# 04_excitation.net
KiCad netlist of a schematic drawn in Altium Designer
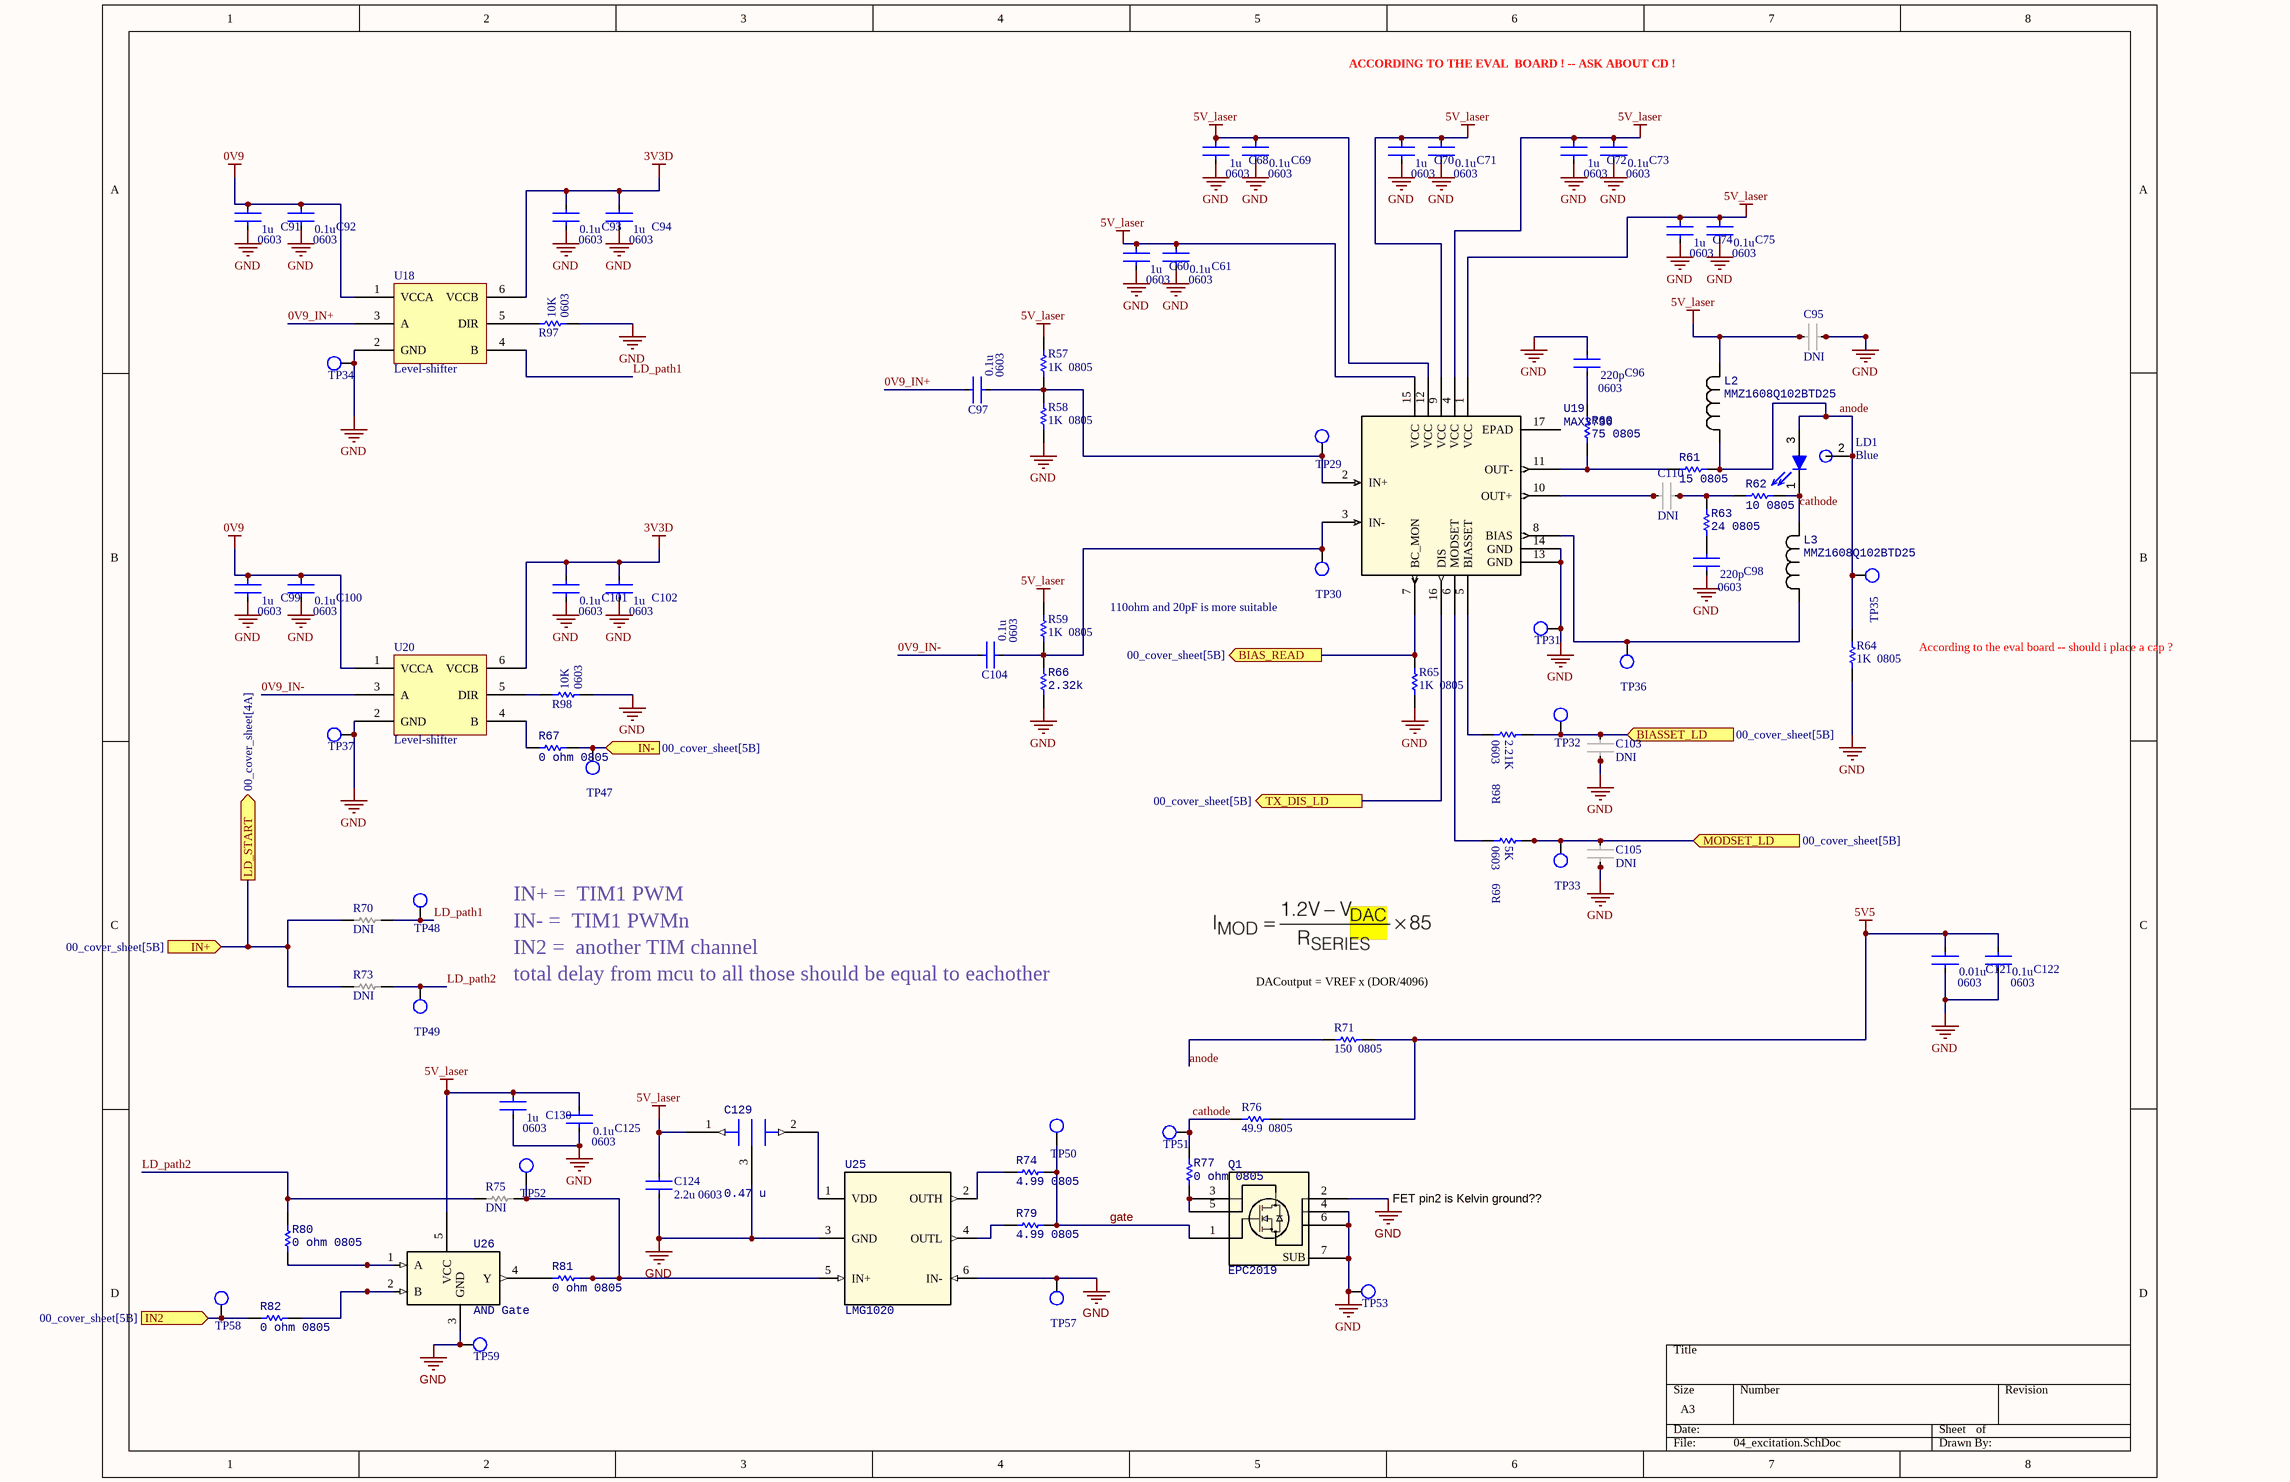
[diagram p0: 04_excitation.SchDoc]

(export (version "E")
  (design (tool "Eeschema 10.0.6"))
  (components
    (comp (ref "C60")
      (value "C1608X5R1E105K080AC")
      (footprint "CAPTDK0603")
      (description "CAP CER 1UF 25V X5R 0603")
      (libsource (lib "tcspc00") (part "C1608X5R1E105K080AC"))
    )
    (comp (ref "C61")
      (value "CGA3E2X7R1H104K080AA")
      (footprint "CAPTDK0603")
      (description "CAP CER 0.1UF 50V X7R 0603")
      (libsource (lib "tcspc00") (part "CGA3E2X7R1H104K080AA"))
    )
    (comp (ref "C68")
      (value "C1608X5R1E105K080AC")
      (footprint "CAPTDK0603")
      (description "CAP CER 1UF 25V X5R 0603")
      (libsource (lib "tcspc00") (part "C1608X5R1E105K080AC"))
    )
    (comp (ref "C69")
      (value "CGA3E2X7R1H104K080AA")
      (footprint "CAPTDK0603")
      (description "CAP CER 0.1UF 50V X7R 0603")
      (libsource (lib "tcspc00") (part "CGA3E2X7R1H104K080AA"))
    )
    (comp (ref "C70")
      (value "C1608X5R1E105K080AC")
      (footprint "CAPTDK0603")
      (description "CAP CER 1UF 25V X5R 0603")
      (libsource (lib "tcspc00") (part "C1608X5R1E105K080AC"))
    )
    (comp (ref "C71")
      (value "CGA3E2X7R1H104K080AA")
      (footprint "CAPTDK0603")
      (description "CAP CER 0.1UF 50V X7R 0603")
      (libsource (lib "tcspc00") (part "CGA3E2X7R1H104K080AA"))
    )
    (comp (ref "C72")
      (value "C1608X5R1E105K080AC")
      (footprint "CAPTDK0603")
      (description "CAP CER 1UF 25V X5R 0603")
      (libsource (lib "tcspc00") (part "C1608X5R1E105K080AC"))
    )
    (comp (ref "C73")
      (value "CGA3E2X7R1H104K080AA")
      (footprint "CAPTDK0603")
      (description "CAP CER 0.1UF 50V X7R 0603")
      (libsource (lib "tcspc00") (part "CGA3E2X7R1H104K080AA"))
    )
    (comp (ref "C74")
      (value "C1608X5R1E105K080AC")
      (footprint "CAPTDK0603")
      (description "CAP CER 1UF 25V X5R 0603")
      (libsource (lib "tcspc00") (part "C1608X5R1E105K080AC"))
    )
    (comp (ref "C75")
      (value "CGA3E2X7R1H104K080AA")
      (footprint "CAPTDK0603")
      (description "CAP CER 0.1UF 50V X7R 0603")
      (libsource (lib "tcspc00") (part "CGA3E2X7R1H104K080AA"))
    )
    (comp (ref "C91")
      (value "C1608X5R1E105K080AC")
      (footprint "CAPTDK0603")
      (description "CAP CER 1UF 25V X5R 0603")
      (libsource (lib "tcspc00") (part "C1608X5R1E105K080AC"))
    )
    (comp (ref "C92")
      (value "CGA3E2X7R1H104K080AA")
      (footprint "CAPTDK0603")
      (description "CAP CER 0.1UF 50V X7R 0603")
      (libsource (lib "tcspc00") (part "CGA3E2X7R1H104K080AA"))
    )
    (comp (ref "C93")
      (value "CGA3E2X7R1H104K080AA")
      (footprint "CAPTDK0603")
      (description "CAP CER 0.1UF 50V X7R 0603")
      (libsource (lib "tcspc00") (part "CGA3E2X7R1H104K080AA"))
    )
    (comp (ref "C94")
      (value "C1608X5R1E105K080AC")
      (footprint "CAPTDK0603")
      (description "CAP CER 1UF 25V X5R 0603")
      (libsource (lib "tcspc00") (part "C1608X5R1E105K080AC"))
    )
    (comp (ref "C95")
      (value "DNI")
      (footprint "CAPTDK0603")
      (description "CAP PROVISION 0603")
      (libsource (lib "tcspc00") (part "C0402_PROVISION"))
    )
    (comp (ref "C96")
      (value "C0603C221K5RAC7867")
      (footprint "CAPTDK0603")
      (description "CAP CER 220PF 50V X7R 0603")
      (libsource (lib "tcspc00") (part "C0603C221K5RAC7867"))
    )
    (comp (ref "C97")
      (value "CGA3E2X7R1H104K080AA")
      (footprint "CAPTDK0603")
      (description "CAP CER 0.1UF 50V X7R 0603")
      (libsource (lib "tcspc00") (part "CGA3E2X7R1H104K080AA"))
    )
    (comp (ref "C98")
      (value "C0603C221K5RAC7867")
      (footprint "CAPTDK0603")
      (description "CAP CER 220PF 50V X7R 0603")
      (libsource (lib "tcspc00") (part "C0603C221K5RAC7867"))
    )
    (comp (ref "C99")
      (value "C1608X5R1E105K080AC")
      (footprint "CAPTDK0603")
      (description "CAP CER 1UF 25V X5R 0603")
      (libsource (lib "tcspc00") (part "C1608X5R1E105K080AC"))
    )
    (comp (ref "C100")
      (value "CGA3E2X7R1H104K080AA")
      (footprint "CAPTDK0603")
      (description "CAP CER 0.1UF 50V X7R 0603")
      (libsource (lib "tcspc00") (part "CGA3E2X7R1H104K080AA"))
    )
    (comp (ref "C101")
      (value "CGA3E2X7R1H104K080AA")
      (footprint "CAPTDK0603")
      (description "CAP CER 0.1UF 50V X7R 0603")
      (libsource (lib "tcspc00") (part "CGA3E2X7R1H104K080AA"))
    )
    (comp (ref "C102")
      (value "C1608X5R1E105K080AC")
      (footprint "CAPTDK0603")
      (description "CAP CER 1UF 25V X5R 0603")
      (libsource (lib "tcspc00") (part "C1608X5R1E105K080AC"))
    )
    (comp (ref "C103")
      (value "DNI")
      (footprint "CAPTDK0603")
      (description "CAP PROVISION 0603")
      (libsource (lib "tcspc00") (part "C0402_PROVISION"))
    )
    (comp (ref "C104")
      (value "CGA3E2X7R1H104K080AA")
      (footprint "CAPTDK0603")
      (description "CAP CER 0.1UF 50V X7R 0603")
      (libsource (lib "tcspc00") (part "CGA3E2X7R1H104K080AA"))
    )
    (comp (ref "C105")
      (value "DNI")
      (footprint "CAPTDK0603")
      (description "CAP PROVISION 0603")
      (libsource (lib "tcspc00") (part "C0402_PROVISION"))
    )
    (comp (ref "C110")
      (value "DNI")
      (footprint "CAPTDK0603")
      (description "CAP PROVISION 0603")
      (libsource (lib "tcspc00") (part "C0402_PROVISION"))
    )
    (comp (ref "C121")
      (value "C0603C103J5RACTU")
      (footprint "CAPTDK0603")
      (description "CAP CER 10000PF 50V X7R 0603")
      (libsource (lib "tcspc00") (part "C0603C103J5RACTU"))
    )
    (comp (ref "C122")
      (value "CGA3E2X7R1H104K080AA")
      (footprint "CAPTDK0603")
      (description "CAP CER 0.1UF 50V X7R 0603")
      (libsource (lib "tcspc00") (part "CGA3E2X7R1H104K080AA"))
    )
    (comp (ref "C124")
      (value "2.2u 0603")
      (footprint "CAPTDK0603")
      (description "CAP CER 2.2UF 0603")
      (libsource (lib "tcspc00") (part "CAP2u2"))
    )
    (comp (ref "C125")
      (value "CGA3E2X7R1H104K080AA")
      (footprint "CAPTDK0603")
      (description "CAP CER 0.1UF 50V X7R 0603")
      (libsource (lib "tcspc00") (part "CGA3E2X7R1H104K080AA"))
    )
    (comp (ref "C129")
      (value "0.47 u")
      (footprint "YFF18PW")
      (description "YFF18PW0J474MT0H0N CAP FEEDTHRU 0.47UF 6.3V 0603")
      (libsource (lib "tcspc00") (part "YFF18PW0J474MT0H0N"))
    )
    (comp (ref "C130")
      (value "C1608X5R1E105K080AC")
      (footprint "CAPTDK0603")
      (description "CAP CER 1UF 25V X5R 0603")
      (libsource (lib "tcspc00") (part "C1608X5R1E105K080AC"))
    )
    (comp (ref "L2")
      (value "MMZ1608Q102BTD25")
      (footprint "IND_TDK_MMZ1608_TDK")
      (description "FERRITE BEAD 1K OHM 0603 1LN")
      (libsource (lib "tcspc00") (part "MMZ1608Q102BTD25"))
    )
    (comp (ref "L3")
      (value "MMZ1608Q102BTD25")
      (footprint "IND_TDK_MMZ1608_TDK")
      (description "FERRITE BEAD 1K OHM 0603 1LN")
      (libsource (lib "tcspc00") (part "MMZ1608Q102BTD25"))
    )
    (comp (ref "LD1") (value "Blue") (footprint "LS56HBSM1") (libsource (lib "tcspc00") (part "LA_LS56HB")))
    (comp (ref "Q1")
      (value "EPC2019")
      (footprint "EPC2019_ECC")
      (description "GANFET N-CH 200V 8.5A DIE N-Channel 200 V 8.5A (Ta) Surface Mount Die")
      (libsource (lib "tcspc00") (part "EPC2019"))
    )
    (comp (ref "R57")
      (value "1K  0805")
      (footprint "RES-STACK-POLE-0805")
      (description "RES 1K OHM 1% 1/4W 0805")
      (libsource (lib "tcspc00") (part "RK73H2ATTD1001F"))
    )
    (comp (ref "R58")
      (value "1K  0805")
      (footprint "RES-STACK-POLE-0805")
      (description "RES 1K OHM 1% 1/4W 0805")
      (libsource (lib "tcspc00") (part "RK73H2ATTD1001F"))
    )
    (comp (ref "R59")
      (value "1K  0805")
      (footprint "RES-STACK-POLE-0805")
      (description "RES 1K OHM 1% 1/4W 0805")
      (libsource (lib "tcspc00") (part "RK73H2ATTD1001F"))
    )
    (comp (ref "R60")
      (value "75 0805")
      (footprint "RES-STACK-POLE-0805")
      (description "RES 75 OHM 1% 1/4W 0805")
      (libsource (lib "tcspc00") (part "RK73H2ATTD75R0F"))
    )
    (comp (ref "R61")
      (value "15 0805")
      (footprint "RES-STACK-POLE-0805")
      (description "RES 15 OHM 1% 1/4W 0805")
      (libsource (lib "tcspc00") (part "RK73H2ATTD15R0F"))
    )
    (comp (ref "R62")
      (value "10 0805")
      (footprint "RES-STACK-POLE-0805")
      (description "RES 10 OHM 1% 1/4W 0805")
      (libsource (lib "tcspc00") (part "RK73H2ATTD10R0F"))
    )
    (comp (ref "R63")
      (value "24 0805")
      (footprint "RES-STACK-POLE-0805")
      (description "RES 24 OHM 1% 1/4W 0805")
      (libsource (lib "tcspc00") (part "RK73H2ATTD24R0F"))
    )
    (comp (ref "R64")
      (value "1K  0805")
      (footprint "RES-STACK-POLE-0805")
      (description "RES 1K OHM 1% 1/4W 0805")
      (libsource (lib "tcspc00") (part "RK73H2ATTD1001F"))
    )
    (comp (ref "R65")
      (value "1K  0805")
      (footprint "RES-STACK-POLE-0805")
      (description "RK73H2ATK001KIT %1 tolerance resistors 0805")
      (libsource (lib "tcspc00") (part "RK73H2AT1001F"))
    )
    (comp (ref "R66")
      (value "2.32k")
      (footprint "RES-STACK-POLE-0805")
      (description "RES 2.32K OHM 1% 1/4W 0805")
      (libsource (lib "tcspc00") (part "RK73H2ATTD2321F"))
    )
    (comp (ref "R67")
      (value "0 ohm 0805")
      (footprint "RES-STACK-POLE-0805")
      (description "RES 0 OHM JUMPER 1/8W 0805")
      (libsource (lib "tcspc00") (part "RC0805JR-070RL"))
    )
    (comp (ref "R68")
      (value "RMCF0603FT2K21")
      (footprint "RES-STACK-POLE-0603")
      (description "RES 2.21K OHM 0.1% 1/10W 0603")
      (libsource (lib "tcspc00") (part "RMCF0603FT2K21"))
    )
    (comp (ref "R69")
      (value "RT0603BRE075KL")
      (footprint "RES-STACK-POLE-0603")
      (description "RES 5K OHM 0.1% 1/10W 0603")
      (libsource (lib "tcspc00") (part "RT0603BRE075KL"))
    )
    (comp (ref "R70")
      (value "DNI")
      (footprint "RES-STACK-POLE-0805")
      (description "RES DNI 0805")
      (libsource (lib "tcspc00") (part "R0805"))
    )
    (comp (ref "R71")
      (value "150  0805")
      (footprint "RES-STACK-POLE-0805")
      (description "RES 150 OHM 1% 1/4W 0805")
      (libsource (lib "tcspc00") (part "RK73H2ATTD1500F"))
    )
    (comp (ref "R73")
      (value "DNI")
      (footprint "RES-STACK-POLE-0805")
      (description "RES DNI 0805")
      (libsource (lib "tcspc00") (part "R0805"))
    )
    (comp (ref "R74")
      (value "4.99 0805")
      (footprint "RES-STACK-POLE-0805")
      (description "RES 4.99 OHM 1% 1/4W 0805")
      (libsource (lib "tcspc00") (part "RK73H2ATTD4R99F"))
    )
    (comp (ref "R75")
      (value "DNI")
      (footprint "RES-STACK-POLE-0805")
      (description "RES DNI 0805")
      (libsource (lib "tcspc00") (part "R0805"))
    )
    (comp (ref "R76")
      (value "49.9  0805")
      (footprint "RES-STACK-POLE-0805")
      (description "RES 49.9 OHM 1% 1/4W 0805")
      (libsource (lib "tcspc00") (part "RK73H2ATTD49R9F"))
    )
    (comp (ref "R77")
      (value "0 ohm 0805")
      (footprint "RES-STACK-POLE-0805")
      (description "RES 0 OHM JUMPER 1/8W 0805")
      (libsource (lib "tcspc00") (part "RC0805JR-070RL"))
    )
    (comp (ref "R79")
      (value "4.99 0805")
      (footprint "RES-STACK-POLE-0805")
      (description "RES 4.99 OHM 1% 1/4W 0805")
      (libsource (lib "tcspc00") (part "RK73H2ATTD4R99F"))
    )
    (comp (ref "R80")
      (value "0 ohm 0805")
      (footprint "RES-STACK-POLE-0805")
      (description "RES 0 OHM JUMPER 1/8W 0805")
      (libsource (lib "tcspc00") (part "RC0805JR-070RL"))
    )
    (comp (ref "R81")
      (value "0 ohm 0805")
      (footprint "RES-STACK-POLE-0805")
      (description "RES 0 OHM JUMPER 1/8W 0805")
      (libsource (lib "tcspc00") (part "RC0805JR-070RL"))
    )
    (comp (ref "R82")
      (value "0 ohm 0805")
      (footprint "RES-STACK-POLE-0805")
      (description "RES 0 OHM JUMPER 1/8W 0805")
      (libsource (lib "tcspc00") (part "RC0805JR-070RL"))
    )
    (comp (ref "R97")
      (value "RMCF0603JG10K0")
      (footprint "RES-STACK-POLE-0603")
      (description "RES 10K OHM 5% 1/10W 0603")
      (libsource (lib "tcspc00") (part "RMCF0603JG10K0"))
    )
    (comp (ref "R98")
      (value "RMCF0603JG10K0")
      (footprint "RES-STACK-POLE-0603")
      (description "RES 10K OHM 5% 1/10W 0603")
      (libsource (lib "tcspc00") (part "RMCF0603JG10K0"))
    )
    (comp (ref "TP29")
      (value "TESTPOINT_S")
      (footprint "TESTPOINT_S")
      (description "Testpoint Surface Pad")
      (libsource (lib "tcspc00") (part "TESTPOINT_S"))
    )
    (comp (ref "TP30")
      (value "TESTPOINT_S")
      (footprint "TESTPOINT_S")
      (description "Testpoint Surface Pad")
      (libsource (lib "tcspc00") (part "TESTPOINT_S"))
    )
    (comp (ref "TP31")
      (value "TESTPOINT_S")
      (footprint "TESTPOINT_S")
      (description "Testpoint Surface Pad")
      (libsource (lib "tcspc00") (part "TESTPOINT_S"))
    )
    (comp (ref "TP32")
      (value "TESTPOINT_S")
      (footprint "TESTPOINT_S")
      (description "Testpoint Surface Pad")
      (libsource (lib "tcspc00") (part "TESTPOINT_S"))
    )
    (comp (ref "TP33")
      (value "TESTPOINT_S")
      (footprint "TESTPOINT_S")
      (description "Testpoint Surface Pad")
      (libsource (lib "tcspc00") (part "TESTPOINT_S"))
    )
    (comp (ref "TP34")
      (value "TESTPOINT_S")
      (footprint "TESTPOINT_S")
      (description "Testpoint Surface Pad")
      (libsource (lib "tcspc00") (part "TESTPOINT_S"))
    )
    (comp (ref "TP35")
      (value "TESTPOINT_S")
      (footprint "TESTPOINT_S")
      (description "Testpoint Surface Pad")
      (libsource (lib "tcspc00") (part "TESTPOINT_S"))
    )
    (comp (ref "TP36")
      (value "TESTPOINT_S")
      (footprint "TESTPOINT_S")
      (description "Testpoint Surface Pad")
      (libsource (lib "tcspc00") (part "TESTPOINT_S"))
    )
    (comp (ref "TP37")
      (value "TESTPOINT_S")
      (footprint "TESTPOINT_S")
      (description "Testpoint Surface Pad")
      (libsource (lib "tcspc00") (part "TESTPOINT_S"))
    )
    (comp (ref "TP47")
      (value "TESTPOINT_S")
      (footprint "TESTPOINT_S")
      (description "Testpoint Surface Pad")
      (libsource (lib "tcspc00") (part "TESTPOINT_S"))
    )
    (comp (ref "TP48")
      (value "TESTPOINT_S")
      (footprint "TESTPOINT_S")
      (description "Testpoint Surface Pad")
      (libsource (lib "tcspc00") (part "TESTPOINT_S"))
    )
    (comp (ref "TP49")
      (value "TESTPOINT_S")
      (footprint "TESTPOINT_S")
      (description "Testpoint Surface Pad")
      (libsource (lib "tcspc00") (part "TESTPOINT_S"))
    )
    (comp (ref "TP50")
      (value "TESTPOINT_S")
      (footprint "TESTPOINT_S")
      (description "Testpoint Surface Pad")
      (libsource (lib "tcspc00") (part "TESTPOINT_S"))
    )
    (comp (ref "TP51")
      (value "TESTPOINT_S")
      (footprint "TESTPOINT_S")
      (description "Testpoint Surface Pad")
      (libsource (lib "tcspc00") (part "TESTPOINT_S"))
    )
    (comp (ref "TP52")
      (value "TESTPOINT_S")
      (footprint "TESTPOINT_S")
      (description "Testpoint Surface Pad")
      (libsource (lib "tcspc00") (part "TESTPOINT_S"))
    )
    (comp (ref "TP53")
      (value "TESTPOINT_S")
      (footprint "TESTPOINT_S")
      (description "Testpoint Surface Pad")
      (libsource (lib "tcspc00") (part "TESTPOINT_S"))
    )
    (comp (ref "TP57")
      (value "TESTPOINT_S")
      (footprint "TESTPOINT_S")
      (description "Testpoint Surface Pad")
      (libsource (lib "tcspc00") (part "TESTPOINT_S"))
    )
    (comp (ref "TP58")
      (value "TESTPOINT_S")
      (footprint "TESTPOINT_S")
      (description "Testpoint Surface Pad")
      (libsource (lib "Schlib1") (part "TESTPOINT_S"))
    )
    (comp (ref "TP59")
      (value "TESTPOINT_S")
      (footprint "TESTPOINT_S")
      (description "Testpoint Surface Pad")
      (libsource (lib "tcspc00") (part "TESTPOINT_S"))
    )
    (comp (ref "U18")
      (value "Level-shifter")
      (footprint "SON50P100X60-6N")
      (description "IC TRANSLTR BIDIRECTIONAL 6SON SN74AXCH1T45DRY2 texas instruments")
      (libsource (lib "tcspc00") (part "SN74AXCH1T45DRY2"))
    )
    (comp (ref "U19")
      (value "MAX3736")
      (footprint "16-TQFN-EP")
      (description "IC LASER DRVR 3.2GB 3.63V 16TQFN")
      (libsource (lib "tcspc00") (part "MAX3736"))
    )
    (comp (ref "U20")
      (value "Level-shifter")
      (footprint "SON50P100X60-6N")
      (description "IC TRANSLTR BIDIRECTIONAL 6SON SN74AXCH1T45DRY2 texas instruments")
      (libsource (lib "tcspc00") (part "SN74AXCH1T45DRY2"))
    )
    (comp (ref "U25")
      (value "LMG1020")
      (footprint "YFF0006AEAE")
      (description "IC GATE DRVR LOW-SIDE 6DSBGA")
      (libsource (lib "tcspc00") (part "LMG1020YFFR"))
    )
    (comp (ref "U26")
      (value "AND Gate")
      (footprint "SOT-1.1")
      (description "IC GATE AND 1CH 2-INP SC70-5")
      (libsource (lib "tcspc00") (part "SN74LVC1G08DCKR"))
    )
  )
  (nets
    (net (code "1") (name "/0V9_IN+") (class "Default")
      (node (ref "C97") (pin "1") (pinfunction "1_1") (pintype "passive"))
      (node (ref "U18") (pin "3") (pinfunction "A_3") (pintype "passive"))
    )
    (net (code "2") (name "/0V9_IN-") (class "Default")
      (node (ref "C104") (pin "1") (pinfunction "1_1") (pintype "passive"))
      (node (ref "U20") (pin "3") (pinfunction "A_3") (pintype "passive"))
    )
    (net (code "3") (name "/BIASSET_LD") (class "Default")
      (node (ref "C103") (pin "1") (pinfunction "1_1") (pintype "passive"))
      (node (ref "R68") (pin "2") (pinfunction "2_2") (pintype "passive"))
      (node (ref "TP32") (pin "1") (pinfunction "1_1") (pintype "passive"))
    )
    (net (code "4") (name "/BIAS_READ") (class "Default")
      (node (ref "R65") (pin "2") (pinfunction "2_2") (pintype "passive"))
      (node (ref "U19") (pin "7") (pinfunction "BC_MON_7") (pintype "output"))
    )
    (net (code "5") (name "/IN+") (class "Default")
      (node (ref "R70") (pin "1") (pinfunction "1_1") (pintype "passive"))
      (node (ref "R73") (pin "1") (pinfunction "1_1") (pintype "passive"))
    )
    (net (code "6") (name "/IN-") (class "Default")
      (node (ref "R67") (pin "2") (pinfunction "2_2") (pintype "passive"))
      (node (ref "TP47") (pin "1") (pinfunction "1_1") (pintype "passive"))
    )
    (net (code "7") (name "/IN2") (class "Default")
      (node (ref "R82") (pin "1") (pinfunction "1_1") (pintype "passive"))
      (node (ref "TP58") (pin "1") (pinfunction "1_1") (pintype "passive"))
    )
    (net (code "8") (name "/LD_path1") (class "Default")
      (node (ref "R70") (pin "2") (pinfunction "2_2") (pintype "passive"))
      (node (ref "TP48") (pin "1") (pinfunction "1_1") (pintype "passive"))
      (node (ref "U18") (pin "4") (pinfunction "B_4") (pintype "passive"))
    )
    (net (code "9") (name "/LD_path2") (class "Default")
      (node (ref "R73") (pin "2") (pinfunction "2_2") (pintype "passive"))
      (node (ref "R75") (pin "1") (pinfunction "1_1") (pintype "passive"))
      (node (ref "R80") (pin "2") (pinfunction "2_2") (pintype "passive"))
      (node (ref "TP49") (pin "1") (pinfunction "1_1") (pintype "passive"))
    )
    (net (code "10") (name "/MODSET_LD") (class "Default")
      (node (ref "C105") (pin "1") (pinfunction "1_1") (pintype "passive"))
      (node (ref "R69") (pin "2") (pinfunction "2_2") (pintype "passive"))
      (node (ref "TP33") (pin "1") (pinfunction "1_1") (pintype "passive"))
    )
    (net (code "11") (name "/TX_DIS_LD") (class "Default")
      (node (ref "U19") (pin "16") (pinfunction "DIS_16") (pintype "output"))
    )
    (net (code "12") (name "/anode") (class "Default")
      (node (ref "L2") (pin "2") (pinfunction "2_2") (pintype "passive"))
      (node (ref "LD1") (pin "2") (pintype "passive"))
      (node (ref "LD1") (pin "3") (pintype "passive"))
      (node (ref "R61") (pin "2") (pinfunction "2_2") (pintype "passive"))
      (node (ref "R64") (pin "2") (pinfunction "2_2") (pintype "passive"))
      (node (ref "R71") (pin "1") (pinfunction "1_1") (pintype "passive"))
      (node (ref "TP35") (pin "1") (pinfunction "1_1") (pintype "passive"))
    )
    (net (code "13") (name "/cathode") (class "Default")
      (node (ref "L3") (pin "1") (pinfunction "1_1") (pintype "passive"))
      (node (ref "LD1") (pin "1") (pintype "passive"))
      (node (ref "R62") (pin "2") (pinfunction "2_2") (pintype "passive"))
      (node (ref "R76") (pin "1") (pinfunction "1_1") (pintype "passive"))
      (node (ref "R77") (pin "2") (pinfunction "2_2") (pintype "passive"))
      (node (ref "TP51") (pin "1") (pinfunction "1_1") (pintype "passive"))
    )
    (net (code "14") (name "/gate") (class "Default")
      (node (ref "Q1") (pin "1") (pinfunction "1_1") (pintype "passive"))
      (node (ref "R74") (pin "2") (pinfunction "2_2") (pintype "passive"))
      (node (ref "R79") (pin "2") (pinfunction "2_2") (pintype "passive"))
      (node (ref "TP50") (pin "1") (pinfunction "1_1") (pintype "passive"))
    )
    (net (code "15") (name "0V9") (class "Default")
      (node (ref "C100") (pin "1") (pinfunction "1_1") (pintype "passive"))
      (node (ref "C91") (pin "1") (pinfunction "1_1") (pintype "passive"))
      (node (ref "C92") (pin "1") (pinfunction "1_1") (pintype "passive"))
      (node (ref "C99") (pin "1") (pinfunction "1_1") (pintype "passive"))
      (node (ref "U18") (pin "1") (pinfunction "VCCA_1") (pintype "passive"))
      (node (ref "U20") (pin "1") (pinfunction "VCCA_1") (pintype "passive"))
    )
    (net (code "16") (name "3V3D") (class "Default")
      (node (ref "C101") (pin "1") (pinfunction "1_1") (pintype "passive"))
      (node (ref "C102") (pin "1") (pinfunction "1_1") (pintype "passive"))
      (node (ref "C93") (pin "1") (pinfunction "1_1") (pintype "passive"))
      (node (ref "C94") (pin "1") (pinfunction "1_1") (pintype "passive"))
      (node (ref "U18") (pin "6") (pinfunction "VCCB_6") (pintype "passive"))
      (node (ref "U20") (pin "6") (pinfunction "VCCB_6") (pintype "passive"))
    )
    (net (code "17") (name "5V5") (class "Default")
      (node (ref "C121") (pin "1") (pinfunction "1_1") (pintype "passive"))
      (node (ref "C122") (pin "1") (pinfunction "1_1") (pintype "passive"))
      (node (ref "R71") (pin "2") (pinfunction "2_2") (pintype "passive"))
      (node (ref "R76") (pin "2") (pinfunction "2_2") (pintype "passive"))
    )
    (net (code "18") (name "5V_laser") (class "Default")
      (node (ref "C124") (pin "1") (pinfunction "1_1") (pintype "passive"))
      (node (ref "C125") (pin "1") (pinfunction "1_1") (pintype "passive"))
      (node (ref "C129") (pin "1") (pinfunction "IN/OUT_1") (pintype "output"))
      (node (ref "C130") (pin "1") (pinfunction "1_1") (pintype "passive"))
      (node (ref "C60") (pin "1") (pinfunction "1_1") (pintype "passive"))
      (node (ref "C61") (pin "1") (pinfunction "1_1") (pintype "passive"))
      (node (ref "C68") (pin "1") (pinfunction "1_1") (pintype "passive"))
      (node (ref "C69") (pin "1") (pinfunction "1_1") (pintype "passive"))
      (node (ref "C70") (pin "1") (pinfunction "1_1") (pintype "passive"))
      (node (ref "C71") (pin "1") (pinfunction "1_1") (pintype "passive"))
      (node (ref "C72") (pin "1") (pinfunction "1_1") (pintype "passive"))
      (node (ref "C73") (pin "1") (pinfunction "1_1") (pintype "passive"))
      (node (ref "C74") (pin "1") (pinfunction "1_1") (pintype "passive"))
      (node (ref "C75") (pin "1") (pinfunction "1_1") (pintype "passive"))
      (node (ref "C95") (pin "1") (pinfunction "1_1") (pintype "passive"))
      (node (ref "L2") (pin "1") (pinfunction "1_1") (pintype "passive"))
      (node (ref "R57") (pin "2") (pinfunction "2_2") (pintype "passive"))
      (node (ref "R59") (pin "2") (pinfunction "2_2") (pintype "passive"))
      (node (ref "U19") (pin "1") (pinfunction "VCC_1") (pintype "power_in"))
      (node (ref "U19") (pin "12") (pinfunction "VCC_12") (pintype "power_in"))
      (node (ref "U19") (pin "15") (pinfunction "VCC_15") (pintype "power_in"))
      (node (ref "U19") (pin "4") (pinfunction "VCC_4") (pintype "power_in"))
      (node (ref "U19") (pin "9") (pinfunction "VCC_9") (pintype "power_in"))
      (node (ref "U26") (pin "5") (pinfunction "VCC_5") (pintype "power_in"))
    )
    (net (code "19") (name "GND") (class "Default")
      (node (ref "C100") (pin "2") (pinfunction "2_2") (pintype "passive"))
      (node (ref "C101") (pin "2") (pinfunction "2_2") (pintype "passive"))
      (node (ref "C102") (pin "2") (pinfunction "2_2") (pintype "passive"))
      (node (ref "C103") (pin "2") (pinfunction "2_2") (pintype "passive"))
      (node (ref "C105") (pin "2") (pinfunction "2_2") (pintype "passive"))
      (node (ref "C121") (pin "2") (pinfunction "2_2") (pintype "passive"))
      (node (ref "C122") (pin "2") (pinfunction "2_2") (pintype "passive"))
      (node (ref "C124") (pin "2") (pinfunction "2_2") (pintype "passive"))
      (node (ref "C125") (pin "2") (pinfunction "2_2") (pintype "passive"))
      (node (ref "C129") (pin "3") (pinfunction "GND_3") (pintype "power_in"))
      (node (ref "C130") (pin "2") (pinfunction "2_2") (pintype "passive"))
      (node (ref "C60") (pin "2") (pinfunction "2_2") (pintype "passive"))
      (node (ref "C61") (pin "2") (pinfunction "2_2") (pintype "passive"))
      (node (ref "C68") (pin "2") (pinfunction "2_2") (pintype "passive"))
      (node (ref "C69") (pin "2") (pinfunction "2_2") (pintype "passive"))
      (node (ref "C70") (pin "2") (pinfunction "2_2") (pintype "passive"))
      (node (ref "C71") (pin "2") (pinfunction "2_2") (pintype "passive"))
      (node (ref "C72") (pin "2") (pinfunction "2_2") (pintype "passive"))
      (node (ref "C73") (pin "2") (pinfunction "2_2") (pintype "passive"))
      (node (ref "C74") (pin "2") (pinfunction "2_2") (pintype "passive"))
      (node (ref "C75") (pin "2") (pinfunction "2_2") (pintype "passive"))
      (node (ref "C91") (pin "2") (pinfunction "2_2") (pintype "passive"))
      (node (ref "C92") (pin "2") (pinfunction "2_2") (pintype "passive"))
      (node (ref "C93") (pin "2") (pinfunction "2_2") (pintype "passive"))
      (node (ref "C94") (pin "2") (pinfunction "2_2") (pintype "passive"))
      (node (ref "C95") (pin "2") (pinfunction "2_2") (pintype "passive"))
      (node (ref "C96") (pin "1") (pinfunction "1_1") (pintype "passive"))
      (node (ref "C98") (pin "2") (pinfunction "2_2") (pintype "passive"))
      (node (ref "C99") (pin "2") (pinfunction "2_2") (pintype "passive"))
      (node (ref "Q1") (pin "2") (pinfunction "2_2") (pintype "passive"))
      (node (ref "Q1") (pin "4") (pinfunction "4_4") (pintype "passive"))
      (node (ref "Q1") (pin "6") (pinfunction "6_6") (pintype "passive"))
      (node (ref "Q1") (pin "7") (pinfunction "7_7") (pintype "passive"))
      (node (ref "R58") (pin "1") (pinfunction "1_1") (pintype "passive"))
      (node (ref "R64") (pin "1") (pinfunction "1_1") (pintype "passive"))
      (node (ref "R65") (pin "1") (pinfunction "1_1") (pintype "passive"))
      (node (ref "R66") (pin "1") (pinfunction "1_1") (pintype "passive"))
      (node (ref "R97") (pin "1") (pinfunction "1_1") (pintype "passive"))
      (node (ref "R98") (pin "1") (pinfunction "1_1") (pintype "passive"))
      (node (ref "TP31") (pin "1") (pinfunction "1_1") (pintype "passive"))
      (node (ref "TP34") (pin "1") (pinfunction "1_1") (pintype "passive"))
      (node (ref "TP37") (pin "1") (pinfunction "1_1") (pintype "passive"))
      (node (ref "TP53") (pin "1") (pinfunction "1_1") (pintype "passive"))
      (node (ref "TP57") (pin "1") (pinfunction "1_1") (pintype "passive"))
      (node (ref "TP59") (pin "1") (pinfunction "1_1") (pintype "passive"))
      (node (ref "U18") (pin "2") (pinfunction "GND_2") (pintype "passive"))
      (node (ref "U19") (pin "13") (pinfunction "GND_13") (pintype "power_in"))
      (node (ref "U19") (pin "14") (pinfunction "GND_14") (pintype "power_in"))
      (node (ref "U20") (pin "2") (pinfunction "GND_2") (pintype "passive"))
      (node (ref "U25") (pin "3") (pinfunction "GND_3") (pintype "power_in"))
      (node (ref "U25") (pin "6") (pinfunction "IN-_6") (pintype "input"))
      (node (ref "U26") (pin "3") (pinfunction "GND_3") (pintype "power_in"))
    )
    (net (code "20") (name "Net-(C96-Pad2)") (class "Default")
      (node (ref "C96") (pin "2") (pinfunction "2_2") (pintype "passive"))
      (node (ref "R60") (pin "2") (pinfunction "2_2") (pintype "passive"))
    )
    (net (code "21") (name "Net-(C98-Pad1)") (class "Default")
      (node (ref "C98") (pin "1") (pinfunction "1_1") (pintype "passive"))
      (node (ref "R63") (pin "1") (pinfunction "1_1") (pintype "passive"))
    )
    (net (code "22") (name "Net-(C110-Pad2)") (class "Default")
      (node (ref "C110") (pin "2") (pinfunction "2_2") (pintype "passive"))
      (node (ref "R62") (pin "1") (pinfunction "1_1") (pintype "passive"))
      (node (ref "R63") (pin "2") (pinfunction "2_2") (pintype "passive"))
    )
    (net (code "23") (name "Net-(C129-OUT{slash}IN)") (class "Default")
      (node (ref "C129") (pin "2") (pinfunction "OUT/IN_2") (pintype "output"))
      (node (ref "U25") (pin "1") (pinfunction "VDD_1") (pintype "power_in"))
    )
    (net (code "24") (name "Net-(Q1-Pad3)") (class "Default")
      (node (ref "Q1") (pin "3") (pinfunction "3_3") (pintype "passive"))
      (node (ref "Q1") (pin "5") (pinfunction "5_5") (pintype "passive"))
      (node (ref "R77") (pin "1") (pinfunction "1_1") (pintype "passive"))
    )
    (net (code "25") (name "Net-(U18-DIR)") (class "Default")
      (node (ref "R97") (pin "2") (pinfunction "2_2") (pintype "passive"))
      (node (ref "U18") (pin "5") (pinfunction "DIR_5") (pintype "passive"))
    )
    (net (code "26") (name "Net-(U19-BIAS)") (class "Default")
      (node (ref "L3") (pin "2") (pinfunction "2_2") (pintype "passive"))
      (node (ref "TP36") (pin "1") (pinfunction "1_1") (pintype "passive"))
      (node (ref "U19") (pin "8") (pinfunction "BIAS_8") (pintype "output"))
    )
    (net (code "27") (name "Net-(U19-BIASSET)") (class "Default")
      (node (ref "R68") (pin "1") (pinfunction "1_1") (pintype "passive"))
      (node (ref "U19") (pin "5") (pinfunction "BIASSET_5") (pintype "passive"))
    )
    (net (code "28") (name "Net-(U19-IN+)") (class "Default")
      (node (ref "C97") (pin "2") (pinfunction "2_2") (pintype "passive"))
      (node (ref "R57") (pin "1") (pinfunction "1_1") (pintype "passive"))
      (node (ref "R58") (pin "2") (pinfunction "2_2") (pintype "passive"))
      (node (ref "TP29") (pin "1") (pinfunction "1_1") (pintype "passive"))
      (node (ref "U19") (pin "2") (pinfunction "IN+_2") (pintype "input"))
    )
    (net (code "29") (name "Net-(U19-IN-)") (class "Default")
      (node (ref "C104") (pin "2") (pinfunction "2_2") (pintype "passive"))
      (node (ref "R59") (pin "1") (pinfunction "1_1") (pintype "passive"))
      (node (ref "R66") (pin "2") (pinfunction "2_2") (pintype "passive"))
      (node (ref "TP30") (pin "1") (pinfunction "1_1") (pintype "passive"))
      (node (ref "U19") (pin "3") (pinfunction "IN-_3") (pintype "input"))
    )
    (net (code "30") (name "Net-(U19-MODSET)") (class "Default")
      (node (ref "R69") (pin "1") (pinfunction "1_1") (pintype "passive"))
      (node (ref "U19") (pin "6") (pinfunction "MODSET_6") (pintype "passive"))
    )
    (net (code "31") (name "Net-(U19-OUT+)") (class "Default")
      (node (ref "C110") (pin "1") (pinfunction "1_1") (pintype "passive"))
      (node (ref "U19") (pin "10") (pinfunction "OUT+_10") (pintype "output"))
    )
    (net (code "32") (name "Net-(U19-OUT-)") (class "Default")
      (node (ref "R60") (pin "1") (pinfunction "1_1") (pintype "passive"))
      (node (ref "R61") (pin "1") (pinfunction "1_1") (pintype "passive"))
      (node (ref "U19") (pin "11") (pinfunction "OUT-_11") (pintype "output"))
    )
    (net (code "33") (name "Net-(U20-B)") (class "Default")
      (node (ref "R67") (pin "1") (pinfunction "1_1") (pintype "passive"))
      (node (ref "U20") (pin "4") (pinfunction "B_4") (pintype "passive"))
    )
    (net (code "34") (name "Net-(U20-DIR)") (class "Default")
      (node (ref "R98") (pin "2") (pinfunction "2_2") (pintype "passive"))
      (node (ref "U20") (pin "5") (pinfunction "DIR_5") (pintype "passive"))
    )
    (net (code "35") (name "Net-(U25-IN+)") (class "Default")
      (node (ref "R75") (pin "2") (pinfunction "2_2") (pintype "passive"))
      (node (ref "R81") (pin "2") (pinfunction "2_2") (pintype "passive"))
      (node (ref "TP52") (pin "1") (pinfunction "1_1") (pintype "passive"))
      (node (ref "U25") (pin "5") (pinfunction "IN+_5") (pintype "input"))
    )
    (net (code "36") (name "Net-(U25-OUTH)") (class "Default")
      (node (ref "R74") (pin "1") (pinfunction "1_1") (pintype "passive"))
      (node (ref "U25") (pin "2") (pinfunction "OUTH_2") (pintype "output"))
    )
    (net (code "37") (name "Net-(U25-OUTL)") (class "Default")
      (node (ref "R79") (pin "1") (pinfunction "1_1") (pintype "passive"))
      (node (ref "U25") (pin "4") (pinfunction "OUTL_4") (pintype "output"))
    )
    (net (code "38") (name "Net-(U26-A)") (class "Default")
      (node (ref "R80") (pin "1") (pinfunction "1_1") (pintype "passive"))
      (node (ref "U26") (pin "1") (pinfunction "A_1") (pintype "input"))
    )
    (net (code "39") (name "Net-(U26-B)") (class "Default")
      (node (ref "R82") (pin "2") (pinfunction "2_2") (pintype "passive"))
      (node (ref "U26") (pin "2") (pinfunction "B_2") (pintype "input"))
    )
    (net (code "40") (name "Net-(U26-Y)") (class "Default")
      (node (ref "R81") (pin "1") (pinfunction "1_1") (pintype "passive"))
      (node (ref "U26") (pin "4") (pinfunction "Y_4") (pintype "output"))
    )
    (net (code "41") (name "unconnected-(U19-EPAD-Pad17)") (class "Default")
      (node (ref "U19") (pin "17") (pinfunction "EPAD_17") (pintype "power_in"))
    )
  )
)
